# MotorController.net
KiCad netlist of a schematic drawn in Altium Designer
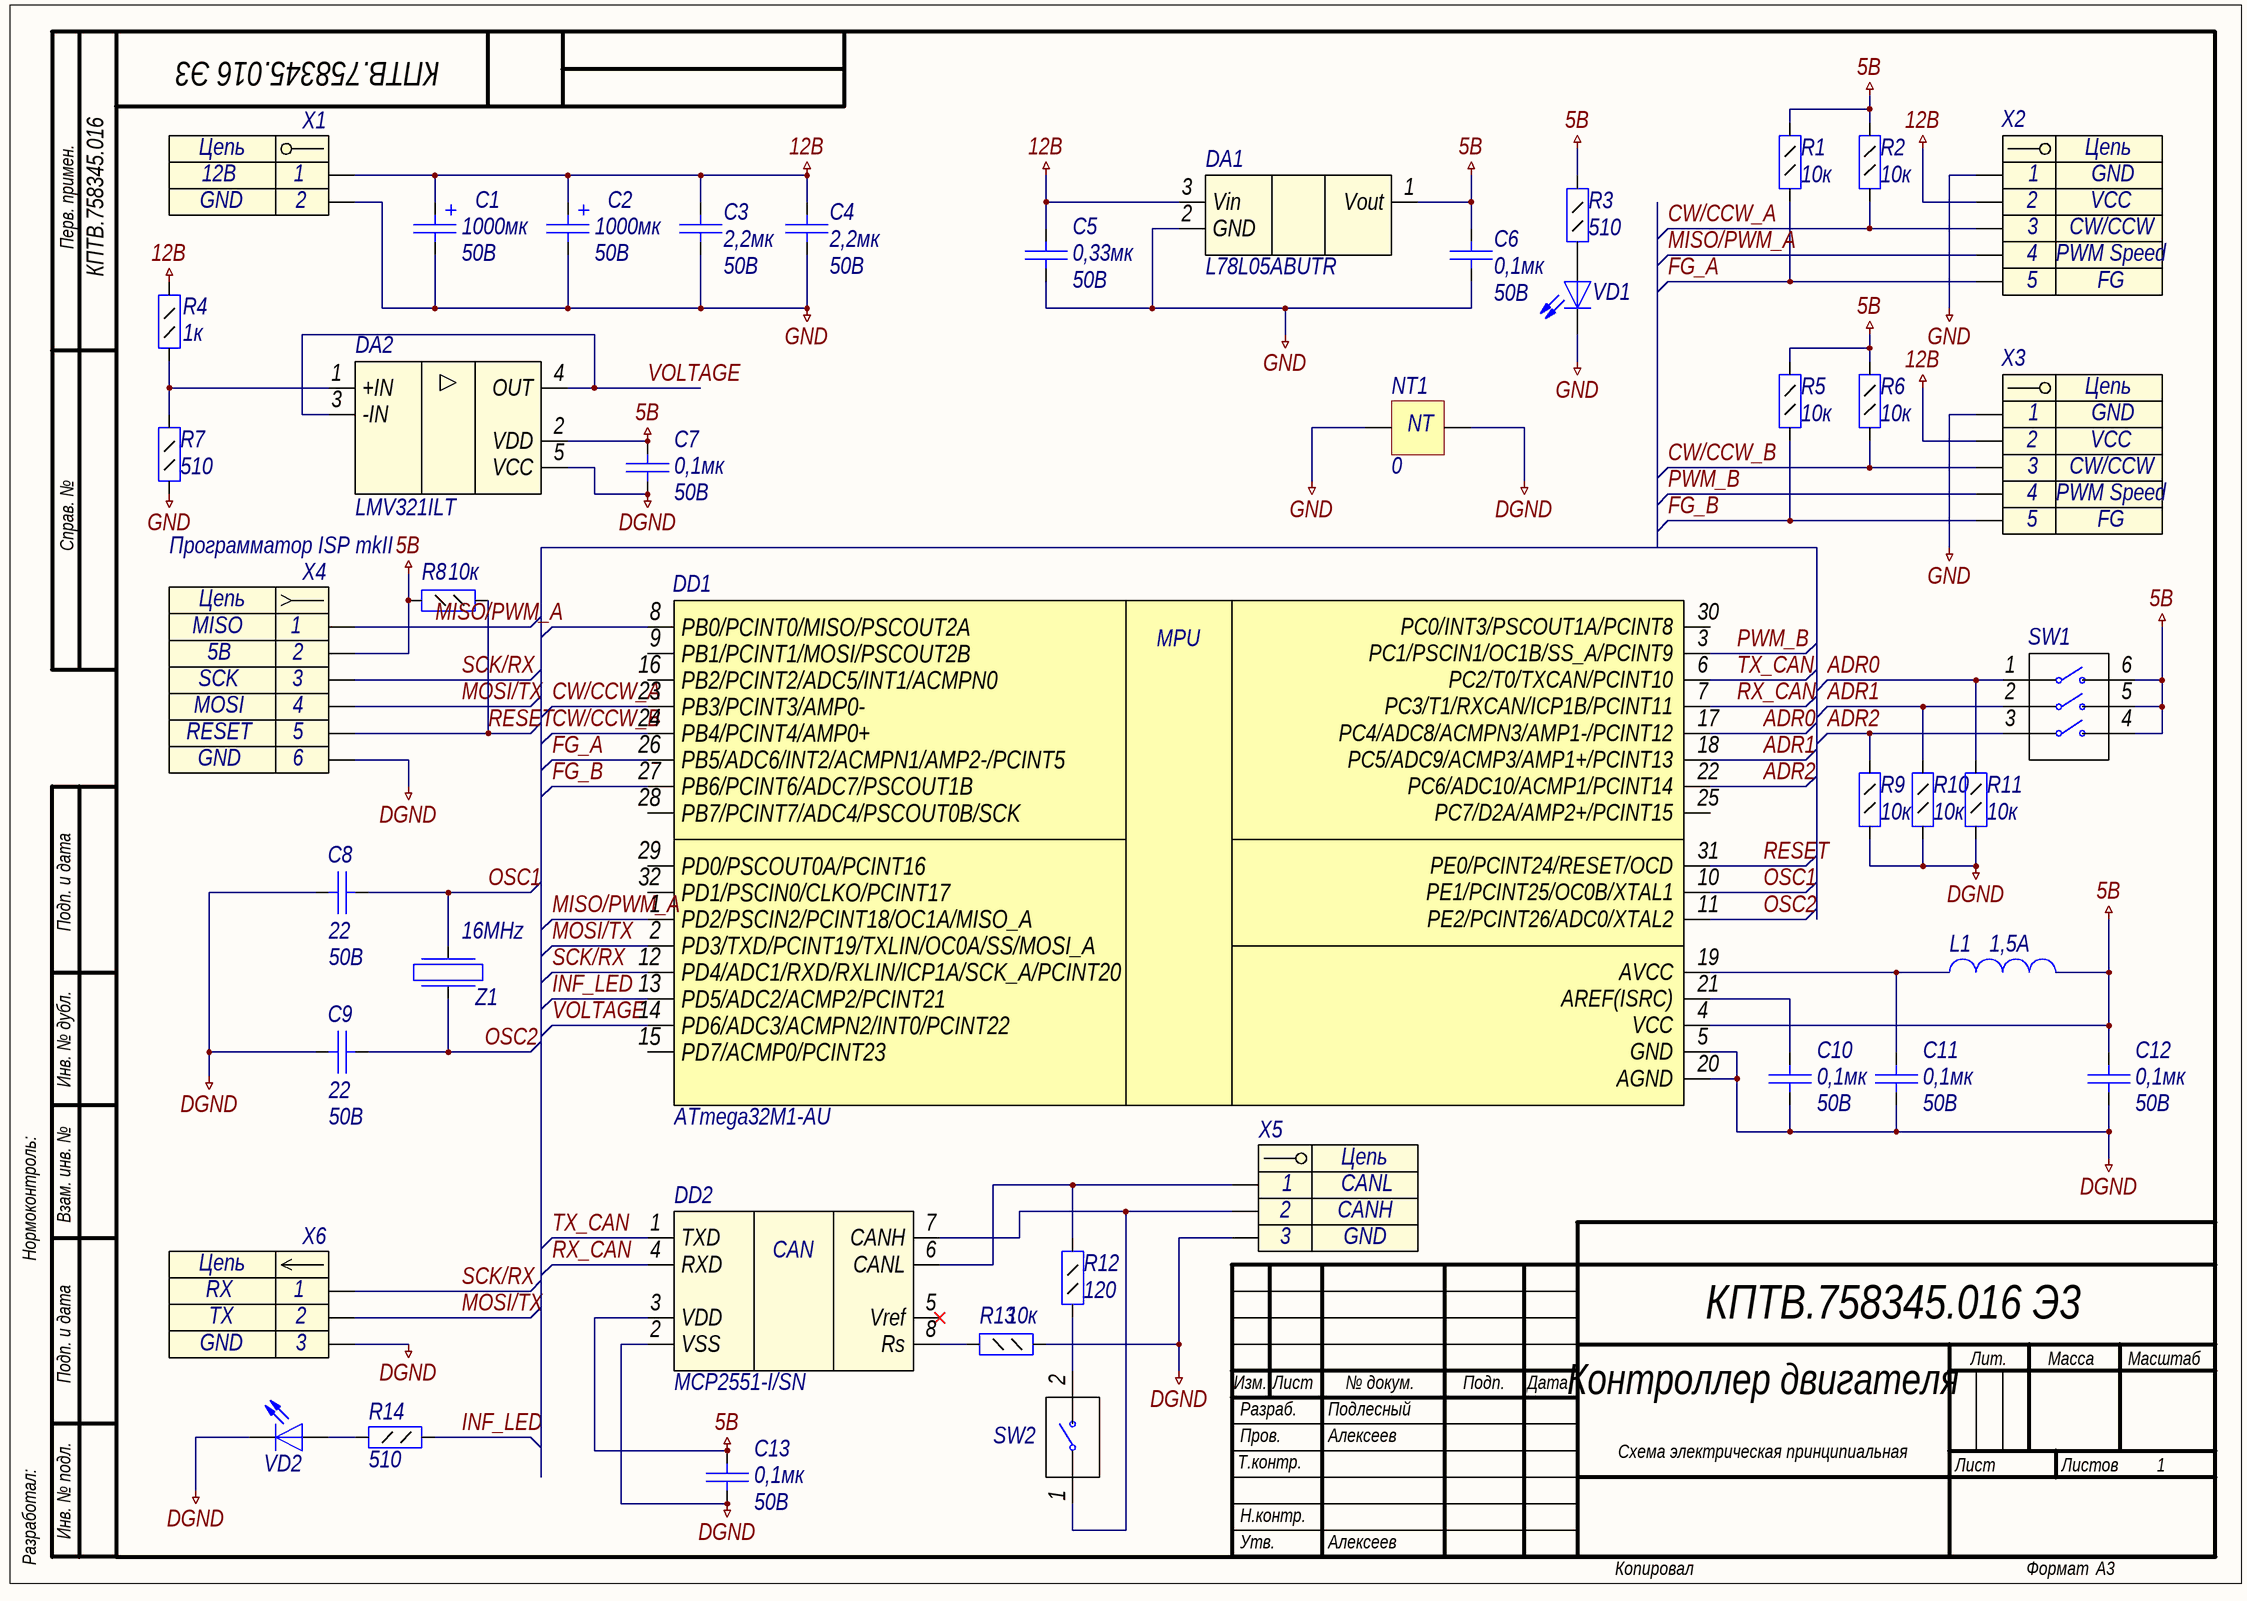
[diagram p0: MotorController.schdoc]

(export (version "E")
  (design (tool "Eeschema 10.0.6"))
  (components
    (comp (ref "C1")
      (value "1000мк")
      (footprint "K50-35(13X25)_V")
      (description "Конденсатор полярный")
      (fields
        (field (name "VOLTAGE") "50В")
        (field (name "PART NUMBER") "TKR102M1HJ21")
        (field (name "Comment") "Capacitor_pol")
      )
      (libsource (lib "MOP44") (part "Capacitor_pol"))
    )
    (comp (ref "C2")
      (value "1000мк")
      (footprint "K50-35(13X25)_V")
      (description "Конденсатор полярный")
      (fields
        (field (name "VOLTAGE") "50В")
        (field (name "PART NUMBER") "TKR102M1HJ21")
        (field (name "Comment") "Capacitor_pol")
      )
      (libsource (lib "MOP44") (part "Capacitor_pol"))
    )
    (comp (ref "C3")
      (value "2,2мк")
      (footprint "C1206")
      (description "Конденсатор")
      (fields
        (field (name "VOLTAGE") "50В")
        (field (name "PART NUMBER") "GRM31CR71H225KA88**L")
        (field (name "Comment") "Capacitor")
      )
      (libsource (lib "MOP44") (part "Capacitor"))
    )
    (comp (ref "C4")
      (value "2,2мк")
      (footprint "C1206")
      (description "Конденсатор")
      (fields
        (field (name "VOLTAGE") "50В")
        (field (name "PART NUMBER") "GRM31CR71H225KA88**L")
        (field (name "Comment") "Capacitor")
      )
      (libsource (lib "MOP44") (part "Capacitor"))
    )
    (comp (ref "C5")
      (value "0,33мк")
      (footprint "C1206")
      (description "Конденсатор")
      (fields
        (field (name "VOLTAGE") "50В")
        (field (name "PART NUMBER") "GRM319R71H334K")
        (field (name "Comment") "Capacitor")
      )
      (libsource (lib "MOP44") (part "Capacitor"))
    )
    (comp (ref "C6")
      (value "0,1мк")
      (footprint "C0805")
      (description "Конденсатор")
      (fields
        (field (name "VOLTAGE") "50В")
        (field (name "PART NUMBER") "GRM21BR71H104KA01L ")
        (field (name "Comment") "Capacitor")
      )
      (libsource (lib "MOP44") (part "Capacitor"))
    )
    (comp (ref "C7")
      (value "0,1мк")
      (footprint "C0805")
      (description "Конденсатор")
      (fields
        (field (name "VOLTAGE") "50В")
        (field (name "PART NUMBER") "GRM21BR71H104KA01L ")
        (field (name "Comment") "Capacitor")
      )
      (libsource (lib "MOP44") (part "Capacitor"))
    )
    (comp (ref "C8")
      (value "22")
      (footprint "C0805")
      (description "Конденсатор")
      (fields
        (field (name "VOLTAGE") "50В")
        (field (name "PART NUMBER") "GRM21A5C2E220JW01D")
        (field (name "Comment") "Capacitor")
      )
      (libsource (lib "MOP44") (part "Capacitor"))
    )
    (comp (ref "C9")
      (value "22")
      (footprint "C0805")
      (description "Конденсатор")
      (fields
        (field (name "VOLTAGE") "50В")
        (field (name "PART NUMBER") "GRM21A5C2E220JW01D")
        (field (name "Comment") "Capacitor")
      )
      (libsource (lib "MOP44") (part "Capacitor"))
    )
    (comp (ref "C10")
      (value "0,1мк")
      (footprint "C0805")
      (description "Конденсатор")
      (fields
        (field (name "VOLTAGE") "50В")
        (field (name "PART NUMBER") "GRM21BR71H104KA01L ")
        (field (name "Comment") "Capacitor")
      )
      (libsource (lib "MOP44") (part "Capacitor"))
    )
    (comp (ref "C11")
      (value "0,1мк")
      (footprint "C0805")
      (description "Конденсатор")
      (fields
        (field (name "VOLTAGE") "50В")
        (field (name "PART NUMBER") "GRM21BR71H104KA01L ")
        (field (name "Comment") "Capacitor")
      )
      (libsource (lib "MOP44") (part "Capacitor"))
    )
    (comp (ref "C12")
      (value "0,1мк")
      (footprint "C0805")
      (description "Конденсатор")
      (fields
        (field (name "VOLTAGE") "50В")
        (field (name "PART NUMBER") "GRM21BR71H104KA01L ")
        (field (name "Comment") "Capacitor")
      )
      (libsource (lib "MOP44") (part "Capacitor"))
    )
    (comp (ref "C13")
      (value "0,1мк")
      (footprint "C0805")
      (description "Конденсатор")
      (fields
        (field (name "VOLTAGE") "50В")
        (field (name "PART NUMBER") "GRM21BR71H104KA01L ")
        (field (name "Comment") "Capacitor")
      )
      (libsource (lib "MOP44") (part "Capacitor"))
    )
    (comp (ref "DA1")
      (value "L78L05ABUTR")
      (footprint "SOT-89-3")
      (description "Cтабилизатор напряжения (+5В; 0.1А), 4%, (-40...+125C)")
      (fields (field (name "MANUFACTURER") "ST Microelectronics"))
      (libsource (lib "MOP44") (part "L78L05ABUTR"))
    )
    (comp (ref "DA2")
      (value "LMV321ILT")
      (footprint "SOT23-5")
      (description "HIGH-DRIVE OPERATIONAL AMPLIFIERS WITH SHUTDOWN")
      (libsource (lib "MOP44") (part "LMV321ILT"))
    )
    (comp (ref "DD1")
      (value "ATmega32M1-AU")
      (footprint "TQFP-32")
      (description "Микроконтроллер 8-Бит, AVR, 16МГц, 32КБ Flash")
      (libsource (lib "MOP44") (part "ATmega32M1-AU"))
    )
    (comp (ref "DD2")
      (value "MCP2551-I/SN")
      (footprint "SO8")
      (description "High-Speed CAN Transceiver")
      (libsource (lib "MOP44") (part "MCP2551-I/SN"))
    )
    (comp (ref "L1")
      (value "Inductor")
      (footprint "L0603")
      (description "EMI Suppression Filter")
      (fields (field (name "RATED CURRENT") "1,5A") (field (name "PART NUMBER") "BLM18PG181SN1D"))
      (libsource (lib "MOP44") (part "Inductor"))
    )
    (comp (ref "NT1") (value "0") (footprint "Pofigistor0603") (libsource (lib "MOP44") (part "Pofigistor")))
    (comp (ref "R1")
      (value "10к")
      (footprint "R0805")
      (description "Резистор")
      (fields (field (name "POWER") "0,125Вт") (field (name "Comment") "Resistor_0,125Вт"))
      (libsource (lib "MOP44") (part "Resistor_0,125Вт"))
    )
    (comp (ref "R2")
      (value "10к")
      (footprint "R0805")
      (description "Резистор")
      (fields (field (name "POWER") "0,125Вт") (field (name "Comment") "Resistor_0,125Вт"))
      (libsource (lib "MOP44") (part "Resistor_0,125Вт"))
    )
    (comp (ref "R3")
      (value "510")
      (footprint "R0805")
      (description "Резистор")
      (fields (field (name "PART NUMBER") "RC0805FR-07510RL") (field (name "POWER") "0,125Вт"))
      (libsource (lib "") (part "Resistor_0,125Вт_2"))
    )
    (comp (ref "R4")
      (value "1к")
      (footprint "R0805")
      (description "Резистор")
      (fields (field (name "PART NUMBER") "RC0805FR-071KL") (field (name "POWER") "0,125Вт"))
      (libsource (lib "") (part "Resistor_0,125Вт_2"))
    )
    (comp (ref "R5")
      (value "10к")
      (footprint "R0805")
      (description "Резистор")
      (fields (field (name "POWER") "0,125Вт") (field (name "Comment") "Resistor_0,125Вт"))
      (libsource (lib "MOP44") (part "Resistor_0,125Вт"))
    )
    (comp (ref "R6")
      (value "10к")
      (footprint "R0805")
      (description "Резистор")
      (fields (field (name "POWER") "0,125Вт") (field (name "Comment") "Resistor_0,125Вт"))
      (libsource (lib "MOP44") (part "Resistor_0,125Вт"))
    )
    (comp (ref "R7")
      (value "510")
      (footprint "R0805")
      (description "Резистор")
      (fields (field (name "PART NUMBER") "RC0805FR-07510RL") (field (name "POWER") "0,125Вт"))
      (libsource (lib "") (part "Resistor_0,125Вт_2"))
    )
    (comp (ref "R8")
      (value "10к")
      (footprint "R0805")
      (description "Резистор")
      (fields (field (name "POWER") "0,125Вт") (field (name "Comment") "Resistor_0,125Вт"))
      (libsource (lib "") (part "Resistor_0,125Вт_1"))
    )
    (comp (ref "R9")
      (value "10к")
      (footprint "R0805")
      (description "Резистор")
      (fields (field (name "POWER") "0,125Вт") (field (name "Comment") "Resistor_0,125Вт"))
      (libsource (lib "MOP44") (part "Resistor_0,125Вт"))
    )
    (comp (ref "R10")
      (value "10к")
      (footprint "R0805")
      (description "Резистор")
      (fields (field (name "POWER") "0,125Вт") (field (name "Comment") "Resistor_0,125Вт"))
      (libsource (lib "MOP44") (part "Resistor_0,125Вт"))
    )
    (comp (ref "R11")
      (value "10к")
      (footprint "R0805")
      (description "Резистор")
      (fields (field (name "POWER") "0,125Вт") (field (name "Comment") "Resistor_0,125Вт"))
      (libsource (lib "MOP44") (part "Resistor_0,125Вт"))
    )
    (comp (ref "R12")
      (value "120")
      (footprint "R0805")
      (description "Резистор")
      (fields (field (name "PART NUMBER") "RC0805FR-07120RL") (field (name "POWER") "0,125Вт"))
      (libsource (lib "") (part "Resistor_0,125Вт_2"))
    )
    (comp (ref "R13")
      (value "10к")
      (footprint "R0805")
      (description "Резистор")
      (fields (field (name "POWER") "0,125Вт") (field (name "Comment") "Resistor_0,125Вт"))
      (libsource (lib "") (part "Resistor_0,125Вт_1"))
    )
    (comp (ref "R14")
      (value "510")
      (footprint "R0805")
      (description "Резистор")
      (fields (field (name "PART NUMBER") "RC0805FR-07510RL") (field (name "POWER") "0,125Вт"))
      (libsource (lib "MOP44") (part "Resistor_0,125Вт"))
    )
    (comp (ref "SW1")
      (value "~")
      (footprint "DIP3")
      (description "DIP переключатель адреса")
      (fields (field (name "PART NUMBER") "DS1040-03RN"))
      (libsource (lib "MOP44") (part "DS1040-03"))
    )
    (comp (ref "SW2")
      (value "DS1040-01")
      (footprint "DIP1")
      (description "DIP переключатель")
      (fields (field (name "PART NUMBER") "DS1040-01RN"))
      (libsource (lib "MOP44") (part "DS1040-01"))
    )
    (comp (ref "VD1")
      (value "LED")
      (footprint "L_0805")
      (description "Светодиод")
      (fields (field (name "PART NUMBER") "KP-2012EC"))
      (libsource (lib "MOP44") (part "LED"))
    )
    (comp (ref "VD2")
      (value "LED")
      (footprint "L_0805")
      (description "Светодиод")
      (fields (field (name "PART NUMBER") "KP-2012EC"))
      (libsource (lib "MOP44") (part "LED"))
    )
    (comp (ref "X1")
      (value "Header_2_trm")
      (footprint "TERMINAL-2WAY-5MM")
      (description "Разъем - 2 конт. клеммник")
      (libsource (lib "MOP44") (part "Header_2_trm"))
    )
    (comp (ref "X2")
      (value "Header_5_trm")
      (footprint "TERMINAL-5WAY-5MM")
      (description "Разъем - 5 конт. клеммник")
      (libsource (lib "MOP44") (part "Header_5_trm"))
    )
    (comp (ref "X3")
      (value "Header_5_trm")
      (footprint "TERMINAL-5WAY-5MM_")
      (description "Разъем - 5 конт. клеммник")
      (libsource (lib "MOP44") (part "Header_5_trm"))
    )
    (comp (ref "X4")
      (value "Программатор ISP mkII")
      (footprint "PLS2-6")
      (description "Разъем - 6 конт. розетка")
      (libsource (lib "MOP44") (part "Header_6_sct"))
    )
    (comp (ref "X5")
      (value "Header_3_trm")
      (footprint "TERMINAL-3WAY-3.5MM")
      (description "Разъем - 3 конт. клеммник")
      (libsource (lib "MOP44") (part "Header_3_trm"))
    )
    (comp (ref "X6")
      (value "Header_3_plg")
      (footprint "PLS-3")
      (description "Разъем - 3 конт. вилка")
      (fields (field (name "PART NUMBER") "DS1021-1*3SF112-B"))
      (libsource (lib "MOP44") (part "Header_3_plg"))
    )
    (comp (ref "Z1")
      (value "Crystal")
      (footprint "HC-49S")
      (description "Кварцевый резонатор")
      (fields (field (name "FREQUENCE") "16MHz") (field (name "PART NUMBER") "16.000MHzHC-49US"))
      (libsource (lib "MOP44") (part "Crystal"))
    )
  )
  (nets
    (net (code "1") (name "/ADR0") (class "Default")
      (node (ref "DD1") (pin "17") (pinfunction "PC4/ADC8/ACMPN3/AMP1-/PCINT12_17") (pintype "passive"))
      (node (ref "R11") (pin "1") (pinfunction "1_1") (pintype "passive"))
      (node (ref "SW1") (pin "1") (pintype "passive"))
    )
    (net (code "2") (name "/ADR1") (class "Default")
      (node (ref "DD1") (pin "18") (pinfunction "PC5/ADC9/ACMP3/AMP1+/PCINT13_18") (pintype "passive"))
      (node (ref "R10") (pin "1") (pinfunction "1_1") (pintype "passive"))
      (node (ref "SW1") (pin "2") (pintype "passive"))
    )
    (net (code "3") (name "/ADR2") (class "Default")
      (node (ref "DD1") (pin "22") (pinfunction "PC6/ADC10/ACMP1/PCINT14_22") (pintype "passive"))
      (node (ref "R9") (pin "1") (pinfunction "1_1") (pintype "passive"))
      (node (ref "SW1") (pin "3") (pintype "passive"))
    )
    (net (code "4") (name "/CW{slash}CCW_A") (class "Default")
      (node (ref "DD1") (pin "23") (pinfunction "PB3/PCINT3/AMP0-_23") (pintype "passive"))
      (node (ref "R2") (pin "2") (pinfunction "2_2") (pintype "passive"))
      (node (ref "X2") (pin "3") (pinfunction "3_3") (pintype "passive"))
    )
    (net (code "5") (name "/CW{slash}CCW_B") (class "Default")
      (node (ref "DD1") (pin "24") (pinfunction "PB4/PCINT4/AMP0+_24") (pintype "passive"))
      (node (ref "R6") (pin "2") (pinfunction "2_2") (pintype "passive"))
      (node (ref "X3") (pin "3") (pinfunction "3_3") (pintype "passive"))
    )
    (net (code "6") (name "/FG_A") (class "Default")
      (node (ref "DD1") (pin "26") (pinfunction "PB5/ADC6/INT2/ACMPN1/AMP2-/PCINT5_26") (pintype "passive"))
      (node (ref "R1") (pin "2") (pinfunction "2_2") (pintype "passive"))
      (node (ref "X2") (pin "5") (pinfunction "5_5") (pintype "passive"))
    )
    (net (code "7") (name "/FG_B") (class "Default")
      (node (ref "DD1") (pin "27") (pinfunction "PB6/PCINT6/ADC7/PSCOUT1B_27") (pintype "passive"))
      (node (ref "R5") (pin "2") (pinfunction "2_2") (pintype "passive"))
      (node (ref "X3") (pin "5") (pinfunction "5_5") (pintype "passive"))
    )
    (net (code "8") (name "/INF_LED") (class "Default")
      (node (ref "DD1") (pin "13") (pinfunction "PD5/ADC2/ACMP2/PCINT21_13") (pintype "passive"))
      (node (ref "R14") (pin "1") (pinfunction "1_1") (pintype "passive"))
    )
    (net (code "9") (name "/MISO{slash}PWM_A") (class "Default")
      (node (ref "DD1") (pin "1") (pinfunction "PD2/PSCIN2/PCINT18/OC1A/MISO_A_1") (pintype "passive"))
      (node (ref "X2") (pin "4") (pinfunction "4_4") (pintype "passive"))
      (node (ref "X4") (pin "1") (pinfunction "1_1") (pintype "passive"))
    )
    (net (code "10") (name "/MOSI{slash}TX") (class "Default")
      (node (ref "DD1") (pin "2") (pinfunction "PD3/TXD/PCINT19/TXLIN/OC0A/SS/MOSI_A_2") (pintype "passive"))
      (node (ref "X4") (pin "4") (pinfunction "4_4") (pintype "passive"))
      (node (ref "X6") (pin "2") (pinfunction "2_2") (pintype "passive"))
    )
    (net (code "11") (name "/OSC1") (class "Default")
      (node (ref "C8") (pin "1") (pinfunction "1_1") (pintype "passive"))
      (node (ref "DD1") (pin "10") (pinfunction "PE1/PCINT25/OC0B/XTAL1_10") (pintype "passive"))
      (node (ref "Z1") (pin "2") (pinfunction "2_2") (pintype "passive"))
    )
    (net (code "12") (name "/OSC2") (class "Default")
      (node (ref "C9") (pin "1") (pinfunction "1_1") (pintype "passive"))
      (node (ref "DD1") (pin "11") (pinfunction "PE2/PCINT26/ADC0/XTAL2_11") (pintype "passive"))
      (node (ref "Z1") (pin "1") (pinfunction "1_1") (pintype "passive"))
    )
    (net (code "13") (name "/PWM_B") (class "Default")
      (node (ref "DD1") (pin "3") (pinfunction "PC1/PSCIN1/OC1B/SS_A/PCINT9_3") (pintype "passive"))
      (node (ref "X3") (pin "4") (pinfunction "4_4") (pintype "passive"))
    )
    (net (code "14") (name "/RESET") (class "Default")
      (node (ref "DD1") (pin "31") (pinfunction "PE0/PCINT24/RESET/OCD_31") (pintype "passive"))
      (node (ref "R8") (pin "1") (pinfunction "1_1") (pintype "passive"))
      (node (ref "X4") (pin "5") (pinfunction "5_5") (pintype "passive"))
    )
    (net (code "15") (name "/RX_CAN") (class "Default")
      (node (ref "DD1") (pin "7") (pinfunction "PC3/T1/RXCAN/ICP1B/PCINT11_7") (pintype "passive"))
      (node (ref "DD2") (pin "4") (pinfunction "RXD_4") (pintype "power_in"))
    )
    (net (code "16") (name "/SCK{slash}RX") (class "Default")
      (node (ref "DD1") (pin "12") (pinfunction "PD4/ADC1/RXD/RXLIN/ICP1A/SCK_A/PCINT20_12") (pintype "passive"))
      (node (ref "X4") (pin "3") (pinfunction "3_3") (pintype "passive"))
      (node (ref "X6") (pin "1") (pinfunction "1_1") (pintype "passive"))
    )
    (net (code "17") (name "/TX_CAN") (class "Default")
      (node (ref "DD1") (pin "6") (pinfunction "PC2/T0/TXCAN/PCINT10_6") (pintype "passive"))
      (node (ref "DD2") (pin "1") (pinfunction "TXD_1") (pintype "power_in"))
    )
    (net (code "18") (name "/VOLTAGE") (class "Default")
      (node (ref "DA2") (pin "3") (pinfunction "-IN_3") (pintype "passive"))
      (node (ref "DA2") (pin "4") (pinfunction "OUT_4") (pintype "passive"))
      (node (ref "DD1") (pin "14") (pinfunction "PD6/ADC3/ACMPN2/INT0/PCINT22_14") (pintype "passive"))
    )
    (net (code "19") (name "5B") (class "Default")
      (node (ref "C12") (pin "2") (pinfunction "2_2") (pintype "passive"))
      (node (ref "C13") (pin "2") (pinfunction "2_2") (pintype "passive"))
      (node (ref "C6") (pin "2") (pinfunction "2_2") (pintype "passive"))
      (node (ref "C7") (pin "2") (pinfunction "2_2") (pintype "passive"))
      (node (ref "DA1") (pin "1") (pinfunction "Vout_1") (pintype "power_in"))
      (node (ref "DA2") (pin "2") (pinfunction "VDD_2") (pintype "passive"))
      (node (ref "DD1") (pin "4") (pinfunction "VCC_4") (pintype "passive"))
      (node (ref "DD2") (pin "3") (pinfunction "VDD_3") (pintype "power_in"))
      (node (ref "L1") (pin "2") (pinfunction "2_2") (pintype "passive"))
      (node (ref "R1") (pin "1") (pinfunction "1_1") (pintype "passive"))
      (node (ref "R2") (pin "1") (pinfunction "1_1") (pintype "passive"))
      (node (ref "R3") (pin "2") (pinfunction "2_2") (pintype "passive"))
      (node (ref "R5") (pin "1") (pinfunction "1_1") (pintype "passive"))
      (node (ref "R6") (pin "1") (pinfunction "1_1") (pintype "passive"))
      (node (ref "R8") (pin "2") (pinfunction "2_2") (pintype "passive"))
      (node (ref "SW1") (pin "4") (pintype "passive"))
      (node (ref "SW1") (pin "5") (pintype "passive"))
      (node (ref "SW1") (pin "6") (pintype "passive"))
      (node (ref "X4") (pin "2") (pinfunction "2_2") (pintype "passive"))
    )
    (net (code "20") (name "12B") (class "Default")
      (node (ref "C1") (pin "1") (pinfunction "1_1") (pintype "passive"))
      (node (ref "C2") (pin "1") (pinfunction "1_1") (pintype "passive"))
      (node (ref "C3") (pin "2") (pinfunction "2_2") (pintype "passive"))
      (node (ref "C4") (pin "2") (pinfunction "2_2") (pintype "passive"))
      (node (ref "C5") (pin "2") (pinfunction "2_2") (pintype "passive"))
      (node (ref "DA1") (pin "3") (pinfunction "Vin_3") (pintype "power_in"))
      (node (ref "R4") (pin "2") (pinfunction "2_2") (pintype "passive"))
      (node (ref "X1") (pin "1") (pinfunction "1_1") (pintype "passive"))
      (node (ref "X2") (pin "2") (pinfunction "2_2") (pintype "passive"))
      (node (ref "X3") (pin "2") (pinfunction "2_2") (pintype "passive"))
    )
    (net (code "21") (name "DGND") (class "Default")
      (node (ref "C10") (pin "1") (pinfunction "1_1") (pintype "passive"))
      (node (ref "C11") (pin "1") (pinfunction "1_1") (pintype "passive"))
      (node (ref "C12") (pin "1") (pinfunction "1_1") (pintype "passive"))
      (node (ref "C13") (pin "1") (pinfunction "1_1") (pintype "passive"))
      (node (ref "C7") (pin "1") (pinfunction "1_1") (pintype "passive"))
      (node (ref "C8") (pin "2") (pinfunction "2_2") (pintype "passive"))
      (node (ref "C9") (pin "2") (pinfunction "2_2") (pintype "passive"))
      (node (ref "DA2") (pin "5") (pinfunction "VCC_5") (pintype "passive"))
      (node (ref "DD1") (pin "20") (pinfunction "AGND_20") (pintype "passive"))
      (node (ref "DD1") (pin "5") (pinfunction "GND_5") (pintype "passive"))
      (node (ref "DD2") (pin "2") (pinfunction "VSS_2") (pintype "power_in"))
      (node (ref "NT1") (pin "2") (pinfunction "2_2") (pintype "passive"))
      (node (ref "R10") (pin "2") (pinfunction "2_2") (pintype "passive"))
      (node (ref "R11") (pin "2") (pinfunction "2_2") (pintype "passive"))
      (node (ref "R13") (pin "1") (pinfunction "1_1") (pintype "passive"))
      (node (ref "R9") (pin "2") (pinfunction "2_2") (pintype "passive"))
      (node (ref "VD2") (pin "1") (pinfunction "K_1") (pintype "passive"))
      (node (ref "X4") (pin "6") (pinfunction "6_6") (pintype "passive"))
      (node (ref "X5") (pin "3") (pinfunction "3_3") (pintype "passive"))
      (node (ref "X6") (pin "3") (pinfunction "3_3") (pintype "passive"))
    )
    (net (code "22") (name "GND") (class "Default")
      (node (ref "C1") (pin "2") (pinfunction "2_2") (pintype "passive"))
      (node (ref "C2") (pin "2") (pinfunction "2_2") (pintype "passive"))
      (node (ref "C3") (pin "1") (pinfunction "1_1") (pintype "passive"))
      (node (ref "C4") (pin "1") (pinfunction "1_1") (pintype "passive"))
      (node (ref "C5") (pin "1") (pinfunction "1_1") (pintype "passive"))
      (node (ref "C6") (pin "1") (pinfunction "1_1") (pintype "passive"))
      (node (ref "DA1") (pin "2") (pinfunction "GND_2") (pintype "power_in"))
      (node (ref "NT1") (pin "1") (pinfunction "1_1") (pintype "passive"))
      (node (ref "R7") (pin "1") (pinfunction "1_1") (pintype "passive"))
      (node (ref "VD1") (pin "1") (pinfunction "K_1") (pintype "passive"))
      (node (ref "X1") (pin "2") (pinfunction "2_2") (pintype "passive"))
      (node (ref "X2") (pin "1") (pinfunction "1_1") (pintype "passive"))
      (node (ref "X3") (pin "1") (pinfunction "1_1") (pintype "passive"))
    )
    (net (code "23") (name "Net-(DA2-+IN)") (class "Default")
      (node (ref "DA2") (pin "1") (pinfunction "+IN_1") (pintype "passive"))
      (node (ref "R4") (pin "1") (pinfunction "1_1") (pintype "passive"))
      (node (ref "R7") (pin "2") (pinfunction "2_2") (pintype "passive"))
    )
    (net (code "24") (name "Net-(DD1-AREF(ISRC))") (class "Default")
      (node (ref "C10") (pin "2") (pinfunction "2_2") (pintype "passive"))
      (node (ref "DD1") (pin "21") (pinfunction "AREF(ISRC)_21") (pintype "passive"))
    )
    (net (code "25") (name "Net-(DD1-AVCC)") (class "Default")
      (node (ref "C11") (pin "2") (pinfunction "2_2") (pintype "passive"))
      (node (ref "DD1") (pin "19") (pinfunction "AVCC_19") (pintype "passive"))
      (node (ref "L1") (pin "1") (pinfunction "1_1") (pintype "passive"))
    )
    (net (code "26") (name "Net-(DD2-CANH)") (class "Default")
      (node (ref "DD2") (pin "7") (pinfunction "CANH_7") (pintype "power_in"))
      (node (ref "SW2") (pin "1") (pintype "passive"))
      (node (ref "X5") (pin "2") (pinfunction "2_2") (pintype "passive"))
    )
    (net (code "27") (name "Net-(DD2-CANL)") (class "Default")
      (node (ref "DD2") (pin "6") (pinfunction "CANL_6") (pintype "power_in"))
      (node (ref "R12") (pin "2") (pinfunction "2_2") (pintype "passive"))
      (node (ref "X5") (pin "1") (pinfunction "1_1") (pintype "passive"))
    )
    (net (code "28") (name "Net-(DD2-Rs)") (class "Default")
      (node (ref "DD2") (pin "8") (pinfunction "Rs_8") (pintype "power_in"))
      (node (ref "R13") (pin "2") (pinfunction "2_2") (pintype "passive"))
    )
    (net (code "29") (name "Net-(R12-Pad1)") (class "Default")
      (node (ref "R12") (pin "1") (pinfunction "1_1") (pintype "passive"))
      (node (ref "SW2") (pin "2") (pintype "passive"))
    )
    (net (code "30") (name "Net-(VD1-A)") (class "Default")
      (node (ref "R3") (pin "1") (pinfunction "1_1") (pintype "passive"))
      (node (ref "VD1") (pin "2") (pinfunction "A_2") (pintype "passive"))
    )
    (net (code "31") (name "Net-(VD2-A)") (class "Default")
      (node (ref "R14") (pin "2") (pinfunction "2_2") (pintype "passive"))
      (node (ref "VD2") (pin "2") (pinfunction "A_2") (pintype "passive"))
    )
    (net (code "32") (name "unconnected-(DD1-PB0{slash}PCINT0{slash}MISO{slash}PSCOUT2A-Pad8)") (class "Default")
      (node (ref "DD1") (pin "8") (pinfunction "PB0/PCINT0/MISO/PSCOUT2A_8") (pintype "passive"))
    )
    (net (code "33") (name "unconnected-(DD1-PB1{slash}PCINT1{slash}MOSI{slash}PSCOUT2B-Pad9)") (class "Default")
      (node (ref "DD1") (pin "9") (pinfunction "PB1/PCINT1/MOSI/PSCOUT2B_9") (pintype "passive"))
    )
    (net (code "34") (name "unconnected-(DD1-PB2{slash}PCINT2{slash}ADC5{slash}INT1{slash}ACMPN0-Pad16)") (class "Default")
      (node (ref "DD1") (pin "16") (pinfunction "PB2/PCINT2/ADC5/INT1/ACMPN0_16") (pintype "passive"))
    )
    (net (code "35") (name "unconnected-(DD1-PB7{slash}PCINT7{slash}ADC4{slash}PSCOUT0B{slash}SCK-Pad28)") (class "Default")
      (node (ref "DD1") (pin "28") (pinfunction "PB7/PCINT7/ADC4/PSCOUT0B/SCK_28") (pintype "passive"))
    )
    (net (code "36") (name "unconnected-(DD1-PC0{slash}INT3{slash}PSCOUT1A{slash}PCINT8-Pad30)") (class "Default")
      (node (ref "DD1") (pin "30") (pinfunction "PC0/INT3/PSCOUT1A/PCINT8_30") (pintype "passive"))
    )
    (net (code "37") (name "unconnected-(DD1-PC7{slash}D2A{slash}AMP2+{slash}PCINT15-Pad25)") (class "Default")
      (node (ref "DD1") (pin "25") (pinfunction "PC7/D2A/AMP2+/PCINT15_25") (pintype "passive"))
    )
    (net (code "38") (name "unconnected-(DD1-PD0{slash}PSCOUT0A{slash}PCINT16-Pad29)") (class "Default")
      (node (ref "DD1") (pin "29") (pinfunction "PD0/PSCOUT0A/PCINT16_29") (pintype "passive"))
    )
    (net (code "39") (name "unconnected-(DD1-PD1{slash}PSCIN0{slash}CLKO{slash}PCINT17-Pad32)") (class "Default")
      (node (ref "DD1") (pin "32") (pinfunction "PD1/PSCIN0/CLKO/PCINT17_32") (pintype "passive"))
    )
    (net (code "40") (name "unconnected-(DD1-PD7{slash}ACMP0{slash}PCINT23-Pad15)") (class "Default")
      (node (ref "DD1") (pin "15") (pinfunction "PD7/ACMP0/PCINT23_15") (pintype "passive"))
    )
    (net (code "41") (name "unconnected-(DD2-Vref-Pad5)") (class "Default")
      (node (ref "DD2") (pin "5") (pinfunction "Vref_5") (pintype "power_in+no_connect"))
    )
  )
)
